# rcsdcard_v1.net
KiCad netlist of a schematic drawn in EAGLE
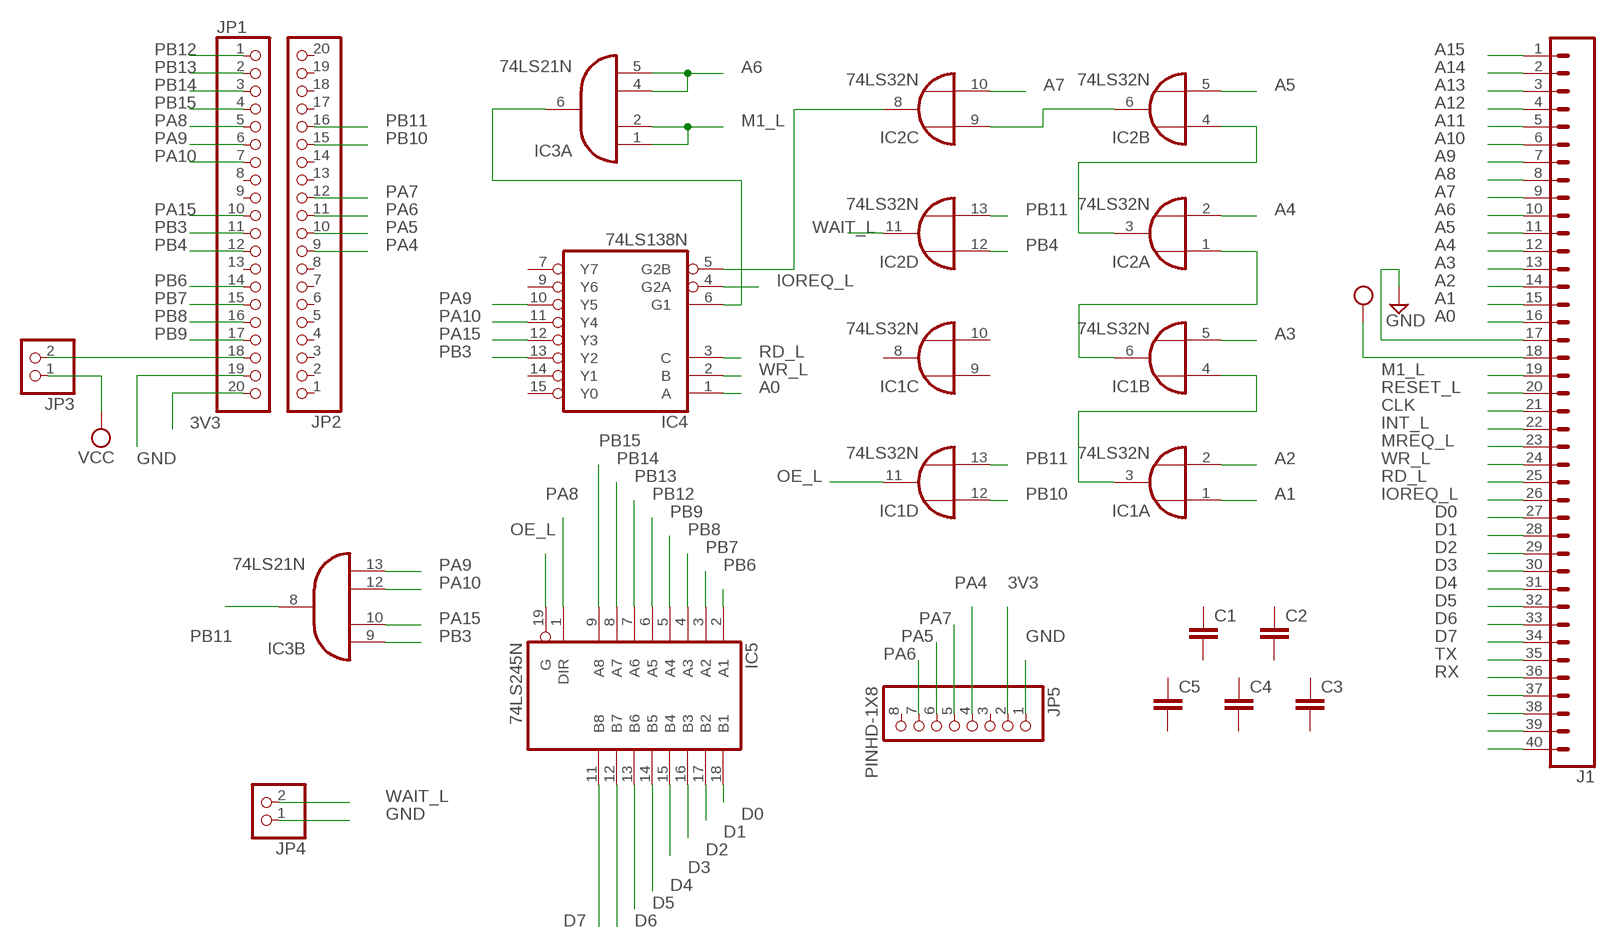
[diagram p0: schematic, sheet 1]

(export (version "E")
  (design (tool "Eeschema 10.0.6"))
  (components
    (comp (ref "C1")
      (value "C-EU050-025X075")
      (footprint "eagle-import:C050-025X075")
      (libsource (lib "eagle-import") (part "C-EU050-025X075"))
    )
    (comp (ref "C2")
      (value "C-EU050-025X075")
      (footprint "eagle-import:C050-025X075")
      (libsource (lib "eagle-import") (part "C-EU050-025X075"))
    )
    (comp (ref "C3")
      (value "C-EU050-025X075")
      (footprint "eagle-import:C050-025X075")
      (libsource (lib "eagle-import") (part "C-EU050-025X075"))
    )
    (comp (ref "C4")
      (value "C-EU050-025X075")
      (footprint "eagle-import:C050-025X075")
      (libsource (lib "eagle-import") (part "C-EU050-025X075"))
    )
    (comp (ref "C5")
      (value "C-EU050-025X075")
      (footprint "eagle-import:C050-025X075")
      (libsource (lib "eagle-import") (part "C-EU050-025X075"))
    )
    (comp (ref "IC1")
      (value "74LS32N")
      (footprint "eagle-import:DIL14")
      (libsource (lib "eagle-import") (part "7432NLS"))
    )
    (comp (ref "IC2")
      (value "74LS32N")
      (footprint "eagle-import:DIL14")
      (libsource (lib "eagle-import") (part "7432NLS"))
    )
    (comp (ref "IC3")
      (value "74LS21N")
      (footprint "eagle-import:DIL14")
      (libsource (lib "eagle-import") (part "7421NLS"))
    )
    (comp (ref "IC4")
      (value "74LS138N")
      (footprint "eagle-import:DIL16")
      (libsource (lib "eagle-import") (part "74138NLS"))
    )
    (comp (ref "IC5")
      (value "74LS245N")
      (footprint "eagle-import:DIL20")
      (libsource (lib "eagle-import") (part "74245NLS"))
    )
    (comp (ref "J1")
      (value "CONN_40OFFSET")
      (footprint "eagle-import:1X40_OFFSET")
      (libsource (lib "eagle-import") (part "CONN_40OFFSET"))
    )
    (comp (ref "JP1")
      (value "PINHD-1X20")
      (footprint "eagle-import:1X20")
      (libsource (lib "eagle-import") (part "PINHD-1X20"))
    )
    (comp (ref "JP2")
      (value "PINHD-1X20")
      (footprint "eagle-import:1X20")
      (libsource (lib "eagle-import") (part "PINHD-1X20"))
    )
    (comp (ref "JP3")
      (value "PINHD-1X2")
      (footprint "eagle-import:1X02")
      (libsource (lib "eagle-import") (part "PINHD-1X2"))
    )
    (comp (ref "JP4")
      (value "PINHD-1X2")
      (footprint "eagle-import:1X02")
      (libsource (lib "eagle-import") (part "PINHD-1X2"))
    )
    (comp (ref "JP5")
      (value "PINHD-1X8")
      (footprint "eagle-import:1X08")
      (libsource (lib "eagle-import") (part "PINHD-1X8"))
    )
  )
  (nets
    (net (code "1") (name "/3V3") (class "Default")
      (node (ref "JP1") (pin "20") (pinfunction "20_20") (pintype "passive"))
      (node (ref "JP5") (pin "2") (pinfunction "2_2") (pintype "passive"))
    )
    (net (code "2") (name "/A0") (class "Default")
      (node (ref "IC4") (pin "1") (pinfunction "A_1") (pintype "input"))
      (node (ref "J1") (pin "16") (pinfunction "16_16") (pintype "passive"))
    )
    (net (code "3") (name "/A1") (class "Default")
      (node (ref "IC1") (pin "1") (pinfunction "I0_1") (pintype "input"))
      (node (ref "J1") (pin "15") (pinfunction "15_15") (pintype "passive"))
    )
    (net (code "4") (name "/A2") (class "Default")
      (node (ref "IC1") (pin "2") (pinfunction "I1_2") (pintype "input"))
      (node (ref "J1") (pin "14") (pinfunction "14_14") (pintype "passive"))
    )
    (net (code "5") (name "/A3") (class "Default")
      (node (ref "IC1") (pin "5") (pinfunction "I1_5") (pintype "input"))
      (node (ref "J1") (pin "13") (pinfunction "13_13") (pintype "passive"))
    )
    (net (code "6") (name "/A4") (class "Default")
      (node (ref "IC2") (pin "2") (pinfunction "I1_2") (pintype "input"))
      (node (ref "J1") (pin "12") (pinfunction "12_12") (pintype "passive"))
    )
    (net (code "7") (name "/A5") (class "Default")
      (node (ref "IC1") (pin "6") (pinfunction "O_6") (pintype "output"))
      (node (ref "IC2") (pin "1") (pinfunction "I0_1") (pintype "input"))
      (node (ref "IC2") (pin "5") (pinfunction "I1_5") (pintype "input"))
      (node (ref "J1") (pin "11") (pinfunction "11_11") (pintype "passive"))
    )
    (net (code "8") (name "/A6") (class "Default")
      (node (ref "IC3") (pin "4") (pinfunction "I2_4") (pintype "input"))
      (node (ref "IC3") (pin "5") (pinfunction "I3_5") (pintype "input"))
      (node (ref "J1") (pin "10") (pinfunction "10_10") (pintype "passive"))
    )
    (net (code "9") (name "/A7") (class "Default")
      (node (ref "IC2") (pin "10") (pinfunction "I1_10") (pintype "input"))
      (node (ref "J1") (pin "9") (pinfunction "9_9") (pintype "passive"))
    )
    (net (code "10") (name "/A8") (class "Default")
      (node (ref "J1") (pin "8") (pinfunction "8_8") (pintype "passive"))
    )
    (net (code "11") (name "/A9") (class "Default")
      (node (ref "J1") (pin "7") (pinfunction "7_7") (pintype "passive"))
    )
    (net (code "12") (name "/A10") (class "Default")
      (node (ref "J1") (pin "6") (pinfunction "6_6") (pintype "passive"))
    )
    (net (code "13") (name "/A11") (class "Default")
      (node (ref "J1") (pin "5") (pinfunction "5_5") (pintype "passive"))
    )
    (net (code "14") (name "/A12") (class "Default")
      (node (ref "J1") (pin "4") (pinfunction "4_4") (pintype "passive"))
    )
    (net (code "15") (name "/A13") (class "Default")
      (node (ref "J1") (pin "3") (pinfunction "3_3") (pintype "passive"))
    )
    (net (code "16") (name "/A14") (class "Default")
      (node (ref "J1") (pin "2") (pinfunction "2_2") (pintype "passive"))
    )
    (net (code "17") (name "/A15") (class "Default")
      (node (ref "J1") (pin "1") (pinfunction "1_1") (pintype "passive"))
    )
    (net (code "18") (name "/CLK") (class "Default")
      (node (ref "J1") (pin "21") (pinfunction "21_21") (pintype "passive"))
    )
    (net (code "19") (name "/D0") (class "Default")
      (node (ref "IC5") (pin "18") (pinfunction "B1_18") (pintype "bidirectional"))
      (node (ref "J1") (pin "27") (pinfunction "27_27") (pintype "passive"))
    )
    (net (code "20") (name "/D1") (class "Default")
      (node (ref "IC5") (pin "17") (pinfunction "B2_17") (pintype "bidirectional"))
      (node (ref "J1") (pin "28") (pinfunction "28_28") (pintype "passive"))
    )
    (net (code "21") (name "/D2") (class "Default")
      (node (ref "IC5") (pin "16") (pinfunction "B3_16") (pintype "bidirectional"))
      (node (ref "J1") (pin "29") (pinfunction "29_29") (pintype "passive"))
    )
    (net (code "22") (name "/D3") (class "Default")
      (node (ref "IC5") (pin "15") (pinfunction "B4_15") (pintype "bidirectional"))
      (node (ref "J1") (pin "30") (pinfunction "30_30") (pintype "passive"))
    )
    (net (code "23") (name "/D4") (class "Default")
      (node (ref "IC5") (pin "14") (pinfunction "B5_14") (pintype "bidirectional"))
      (node (ref "J1") (pin "31") (pinfunction "31_31") (pintype "passive"))
    )
    (net (code "24") (name "/D5") (class "Default")
      (node (ref "IC5") (pin "13") (pinfunction "B6_13") (pintype "bidirectional"))
      (node (ref "J1") (pin "32") (pinfunction "32_32") (pintype "passive"))
    )
    (net (code "25") (name "/D6") (class "Default")
      (node (ref "IC5") (pin "12") (pinfunction "B7_12") (pintype "bidirectional"))
      (node (ref "J1") (pin "33") (pinfunction "33_33") (pintype "passive"))
    )
    (net (code "26") (name "/D7") (class "Default")
      (node (ref "IC5") (pin "11") (pinfunction "B8_11") (pintype "bidirectional"))
      (node (ref "J1") (pin "34") (pinfunction "34_34") (pintype "passive"))
    )
    (net (code "27") (name "/INT_L") (class "Default")
      (node (ref "J1") (pin "22") (pinfunction "22_22") (pintype "passive"))
    )
    (net (code "28") (name "/IOREQ_L") (class "Default")
      (node (ref "IC4") (pin "4") (pinfunction "G2A_4") (pintype "input"))
      (node (ref "J1") (pin "26") (pinfunction "26_26") (pintype "passive"))
    )
    (net (code "29") (name "/M1_L") (class "Default")
      (node (ref "IC3") (pin "1") (pinfunction "I0_1") (pintype "input"))
      (node (ref "IC3") (pin "2") (pinfunction "I1_2") (pintype "input"))
      (node (ref "J1") (pin "19") (pinfunction "19_19") (pintype "passive"))
    )
    (net (code "30") (name "/MREQ_L") (class "Default")
      (node (ref "J1") (pin "23") (pinfunction "23_23") (pintype "passive"))
    )
    (net (code "31") (name "/OE_L") (class "Default")
      (node (ref "IC1") (pin "11") (pinfunction "O_11") (pintype "output"))
      (node (ref "IC5") (pin "19") (pinfunction "G_19") (pintype "input"))
    )
    (net (code "32") (name "/PA4") (class "Default")
      (node (ref "JP2") (pin "9") (pinfunction "9_9") (pintype "passive"))
      (node (ref "JP5") (pin "4") (pinfunction "4_4") (pintype "passive"))
    )
    (net (code "33") (name "/PA5") (class "Default")
      (node (ref "JP2") (pin "10") (pinfunction "10_10") (pintype "passive"))
      (node (ref "JP5") (pin "6") (pinfunction "6_6") (pintype "passive"))
    )
    (net (code "34") (name "/PA6") (class "Default")
      (node (ref "JP2") (pin "11") (pinfunction "11_11") (pintype "passive"))
      (node (ref "JP5") (pin "7") (pinfunction "7_7") (pintype "passive"))
    )
    (net (code "35") (name "/PA7") (class "Default")
      (node (ref "JP2") (pin "12") (pinfunction "12_12") (pintype "passive"))
      (node (ref "JP5") (pin "5") (pinfunction "5_5") (pintype "passive"))
    )
    (net (code "36") (name "/PA8") (class "Default")
      (node (ref "IC5") (pin "1") (pinfunction "DIR_1") (pintype "input"))
      (node (ref "JP1") (pin "5") (pinfunction "5_5") (pintype "passive"))
    )
    (net (code "37") (name "/PA9") (class "Default")
      (node (ref "IC3") (pin "13") (pinfunction "I3_13") (pintype "input"))
      (node (ref "IC4") (pin "10") (pinfunction "Y5_10") (pintype "output"))
      (node (ref "JP1") (pin "6") (pinfunction "6_6") (pintype "passive"))
    )
    (net (code "38") (name "/PA10") (class "Default")
      (node (ref "IC3") (pin "12") (pinfunction "I2_12") (pintype "input"))
      (node (ref "IC4") (pin "11") (pinfunction "Y4_11") (pintype "output"))
      (node (ref "JP1") (pin "7") (pinfunction "7_7") (pintype "passive"))
    )
    (net (code "39") (name "/PA15") (class "Default")
      (node (ref "IC3") (pin "10") (pinfunction "I1_10") (pintype "input"))
      (node (ref "IC4") (pin "12") (pinfunction "Y3_12") (pintype "output"))
      (node (ref "JP1") (pin "10") (pinfunction "10_10") (pintype "passive"))
    )
    (net (code "40") (name "/PB3") (class "Default")
      (node (ref "IC3") (pin "9") (pinfunction "I0_9") (pintype "input"))
      (node (ref "IC4") (pin "13") (pinfunction "Y2_13") (pintype "output"))
      (node (ref "JP1") (pin "11") (pinfunction "11_11") (pintype "passive"))
    )
    (net (code "41") (name "/PB4") (class "Default")
      (node (ref "IC2") (pin "12") (pinfunction "I0_12") (pintype "input"))
      (node (ref "JP1") (pin "12") (pinfunction "12_12") (pintype "passive"))
    )
    (net (code "42") (name "/PB6") (class "Default")
      (node (ref "IC5") (pin "2") (pinfunction "A1_2") (pintype "bidirectional"))
      (node (ref "JP1") (pin "14") (pinfunction "14_14") (pintype "passive"))
    )
    (net (code "43") (name "/PB7") (class "Default")
      (node (ref "IC5") (pin "3") (pinfunction "A2_3") (pintype "bidirectional"))
      (node (ref "JP1") (pin "15") (pinfunction "15_15") (pintype "passive"))
    )
    (net (code "44") (name "/PB8") (class "Default")
      (node (ref "IC5") (pin "4") (pinfunction "A3_4") (pintype "bidirectional"))
      (node (ref "JP1") (pin "16") (pinfunction "16_16") (pintype "passive"))
    )
    (net (code "45") (name "/PB9") (class "Default")
      (node (ref "IC5") (pin "5") (pinfunction "A4_5") (pintype "bidirectional"))
      (node (ref "JP1") (pin "17") (pinfunction "17_17") (pintype "passive"))
    )
    (net (code "46") (name "/PB10") (class "Default")
      (node (ref "IC1") (pin "12") (pinfunction "I0_12") (pintype "input"))
      (node (ref "JP2") (pin "15") (pinfunction "15_15") (pintype "passive"))
    )
    (net (code "47") (name "/PB11") (class "Default")
      (node (ref "IC1") (pin "13") (pinfunction "I1_13") (pintype "input"))
      (node (ref "IC2") (pin "13") (pinfunction "I1_13") (pintype "input"))
      (node (ref "IC3") (pin "8") (pinfunction "O_8") (pintype "output"))
      (node (ref "JP2") (pin "16") (pinfunction "16_16") (pintype "passive"))
    )
    (net (code "48") (name "/PB12") (class "Default")
      (node (ref "IC5") (pin "6") (pinfunction "A5_6") (pintype "bidirectional"))
      (node (ref "JP1") (pin "1") (pinfunction "1_1") (pintype "passive"))
    )
    (net (code "49") (name "/PB13") (class "Default")
      (node (ref "IC5") (pin "7") (pinfunction "A6_7") (pintype "bidirectional"))
      (node (ref "JP1") (pin "2") (pinfunction "2_2") (pintype "passive"))
    )
    (net (code "50") (name "/PB14") (class "Default")
      (node (ref "IC5") (pin "8") (pinfunction "A7_8") (pintype "bidirectional"))
      (node (ref "JP1") (pin "3") (pinfunction "3_3") (pintype "passive"))
    )
    (net (code "51") (name "/PB15") (class "Default")
      (node (ref "IC5") (pin "9") (pinfunction "A8_9") (pintype "bidirectional"))
      (node (ref "JP1") (pin "4") (pinfunction "4_4") (pintype "passive"))
    )
    (net (code "52") (name "/RD_L") (class "Default")
      (node (ref "IC4") (pin "3") (pinfunction "C_3") (pintype "input"))
      (node (ref "J1") (pin "25") (pinfunction "25_25") (pintype "passive"))
    )
    (net (code "53") (name "/RESET_L") (class "Default")
      (node (ref "J1") (pin "20") (pinfunction "20_20") (pintype "passive"))
    )
    (net (code "54") (name "/RX") (class "Default")
      (node (ref "J1") (pin "36") (pinfunction "36_36") (pintype "passive"))
    )
    (net (code "55") (name "/TX") (class "Default")
      (node (ref "J1") (pin "35") (pinfunction "35_35") (pintype "passive"))
    )
    (net (code "56") (name "/WAIT_L") (class "Default")
      (node (ref "IC2") (pin "11") (pinfunction "O_11") (pintype "output"))
      (node (ref "JP4") (pin "2") (pinfunction "2_2") (pintype "passive"))
    )
    (net (code "57") (name "/WR_L") (class "Default")
      (node (ref "IC4") (pin "2") (pinfunction "B_2") (pintype "input"))
      (node (ref "J1") (pin "24") (pinfunction "24_24") (pintype "passive"))
    )
    (net (code "58") (name "GND") (class "Default")
      (node (ref "J1") (pin "17") (pinfunction "17_17") (pintype "passive"))
      (node (ref "JP1") (pin "19") (pinfunction "19_19") (pintype "passive"))
      (node (ref "JP4") (pin "1") (pinfunction "1_1") (pintype "passive"))
      (node (ref "JP5") (pin "1") (pinfunction "1_1") (pintype "passive"))
    )
    (net (code "59") (name "Net-(IC1A-O)") (class "Default")
      (node (ref "IC1") (pin "3") (pinfunction "O_3") (pintype "output"))
      (node (ref "IC1") (pin "4") (pinfunction "I0_4") (pintype "input"))
    )
    (net (code "60") (name "Net-(IC2A-O)") (class "Default")
      (node (ref "IC2") (pin "3") (pinfunction "O_3") (pintype "output"))
      (node (ref "IC2") (pin "4") (pinfunction "I0_4") (pintype "input"))
    )
    (net (code "61") (name "Net-(IC2B-O)") (class "Default")
      (node (ref "IC2") (pin "6") (pinfunction "O_6") (pintype "output"))
      (node (ref "IC2") (pin "9") (pinfunction "I0_9") (pintype "input"))
    )
    (net (code "62") (name "Net-(IC2C-O)") (class "Default")
      (node (ref "IC2") (pin "8") (pinfunction "O_8") (pintype "output"))
      (node (ref "IC4") (pin "5") (pinfunction "G2B_5") (pintype "input"))
    )
    (net (code "63") (name "Net-(IC3A-O)") (class "Default")
      (node (ref "IC3") (pin "6") (pinfunction "O_6") (pintype "output"))
      (node (ref "IC4") (pin "6") (pinfunction "G1_6") (pintype "input"))
    )
    (net (code "64") (name "Net-(JP1-Pad18)") (class "Default")
      (node (ref "JP1") (pin "18") (pinfunction "18_18") (pintype "passive"))
      (node (ref "JP3") (pin "2") (pinfunction "2_2") (pintype "passive"))
    )
    (net (code "65") (name "VCC") (class "Default")
      (node (ref "J1") (pin "18") (pinfunction "18_18") (pintype "passive"))
      (node (ref "JP3") (pin "1") (pinfunction "1_1") (pintype "passive"))
    )
    (net (code "66") (name "unconnected-(C1-Pad1)") (class "Default")
      (node (ref "C1") (pin "1") (pinfunction "1_1") (pintype "passive"))
    )
    (net (code "67") (name "unconnected-(C1-Pad2)") (class "Default")
      (node (ref "C1") (pin "2") (pinfunction "2_2") (pintype "passive"))
    )
    (net (code "68") (name "unconnected-(C2-Pad1)") (class "Default")
      (node (ref "C2") (pin "1") (pinfunction "1_1") (pintype "passive"))
    )
    (net (code "69") (name "unconnected-(C2-Pad2)") (class "Default")
      (node (ref "C2") (pin "2") (pinfunction "2_2") (pintype "passive"))
    )
    (net (code "70") (name "unconnected-(C3-Pad1)") (class "Default")
      (node (ref "C3") (pin "1") (pinfunction "1_1") (pintype "passive"))
    )
    (net (code "71") (name "unconnected-(C3-Pad2)") (class "Default")
      (node (ref "C3") (pin "2") (pinfunction "2_2") (pintype "passive"))
    )
    (net (code "72") (name "unconnected-(C4-Pad1)") (class "Default")
      (node (ref "C4") (pin "1") (pinfunction "1_1") (pintype "passive"))
    )
    (net (code "73") (name "unconnected-(C4-Pad2)") (class "Default")
      (node (ref "C4") (pin "2") (pinfunction "2_2") (pintype "passive"))
    )
    (net (code "74") (name "unconnected-(C5-Pad1)") (class "Default")
      (node (ref "C5") (pin "1") (pinfunction "1_1") (pintype "passive"))
    )
    (net (code "75") (name "unconnected-(C5-Pad2)") (class "Default")
      (node (ref "C5") (pin "2") (pinfunction "2_2") (pintype "passive"))
    )
    (net (code "76") (name "unconnected-(IC1C-I0-Pad9)") (class "Default")
      (node (ref "IC1") (pin "9") (pinfunction "I0_9") (pintype "input"))
    )
    (net (code "77") (name "unconnected-(IC1C-I1-Pad10)") (class "Default")
      (node (ref "IC1") (pin "10") (pinfunction "I1_10") (pintype "input"))
    )
    (net (code "78") (name "unconnected-(IC1C-O-Pad8)") (class "Default")
      (node (ref "IC1") (pin "8") (pinfunction "O_8") (pintype "output"))
    )
    (net (code "79") (name "unconnected-(IC4A-Y0-Pad15)") (class "Default")
      (node (ref "IC4") (pin "15") (pinfunction "Y0_15") (pintype "output"))
    )
    (net (code "80") (name "unconnected-(IC4A-Y1-Pad14)") (class "Default")
      (node (ref "IC4") (pin "14") (pinfunction "Y1_14") (pintype "output"))
    )
    (net (code "81") (name "unconnected-(IC4A-Y6-Pad9)") (class "Default")
      (node (ref "IC4") (pin "9") (pinfunction "Y6_9") (pintype "output"))
    )
    (net (code "82") (name "unconnected-(IC4A-Y7-Pad7)") (class "Default")
      (node (ref "IC4") (pin "7") (pinfunction "Y7_7") (pintype "output"))
    )
    (net (code "83") (name "unconnected-(J1-Pad37)") (class "Default")
      (node (ref "J1") (pin "37") (pinfunction "37_37") (pintype "passive"))
    )
    (net (code "84") (name "unconnected-(J1-Pad38)") (class "Default")
      (node (ref "J1") (pin "38") (pinfunction "38_38") (pintype "passive"))
    )
    (net (code "85") (name "unconnected-(J1-Pad39)") (class "Default")
      (node (ref "J1") (pin "39") (pinfunction "39_39") (pintype "passive"))
    )
    (net (code "86") (name "unconnected-(J1-Pad40)") (class "Default")
      (node (ref "J1") (pin "40") (pinfunction "40_40") (pintype "passive"))
    )
    (net (code "87") (name "unconnected-(JP1-Pad8)") (class "Default")
      (node (ref "JP1") (pin "8") (pinfunction "8_8") (pintype "passive"))
    )
    (net (code "88") (name "unconnected-(JP1-Pad9)") (class "Default")
      (node (ref "JP1") (pin "9") (pinfunction "9_9") (pintype "passive"))
    )
    (net (code "89") (name "unconnected-(JP1-Pad13)") (class "Default")
      (node (ref "JP1") (pin "13") (pinfunction "13_13") (pintype "passive"))
    )
    (net (code "90") (name "unconnected-(JP2-Pad1)") (class "Default")
      (node (ref "JP2") (pin "1") (pinfunction "1_1") (pintype "passive"))
    )
    (net (code "91") (name "unconnected-(JP2-Pad2)") (class "Default")
      (node (ref "JP2") (pin "2") (pinfunction "2_2") (pintype "passive"))
    )
    (net (code "92") (name "unconnected-(JP2-Pad3)") (class "Default")
      (node (ref "JP2") (pin "3") (pinfunction "3_3") (pintype "passive"))
    )
    (net (code "93") (name "unconnected-(JP2-Pad4)") (class "Default")
      (node (ref "JP2") (pin "4") (pinfunction "4_4") (pintype "passive"))
    )
    (net (code "94") (name "unconnected-(JP2-Pad5)") (class "Default")
      (node (ref "JP2") (pin "5") (pinfunction "5_5") (pintype "passive"))
    )
    (net (code "95") (name "unconnected-(JP2-Pad6)") (class "Default")
      (node (ref "JP2") (pin "6") (pinfunction "6_6") (pintype "passive"))
    )
    (net (code "96") (name "unconnected-(JP2-Pad7)") (class "Default")
      (node (ref "JP2") (pin "7") (pinfunction "7_7") (pintype "passive"))
    )
    (net (code "97") (name "unconnected-(JP2-Pad8)") (class "Default")
      (node (ref "JP2") (pin "8") (pinfunction "8_8") (pintype "passive"))
    )
    (net (code "98") (name "unconnected-(JP2-Pad13)") (class "Default")
      (node (ref "JP2") (pin "13") (pinfunction "13_13") (pintype "passive"))
    )
    (net (code "99") (name "unconnected-(JP2-Pad14)") (class "Default")
      (node (ref "JP2") (pin "14") (pinfunction "14_14") (pintype "passive"))
    )
    (net (code "100") (name "unconnected-(JP2-Pad17)") (class "Default")
      (node (ref "JP2") (pin "17") (pinfunction "17_17") (pintype "passive"))
    )
    (net (code "101") (name "unconnected-(JP2-Pad18)") (class "Default")
      (node (ref "JP2") (pin "18") (pinfunction "18_18") (pintype "passive"))
    )
    (net (code "102") (name "unconnected-(JP2-Pad19)") (class "Default")
      (node (ref "JP2") (pin "19") (pinfunction "19_19") (pintype "passive"))
    )
    (net (code "103") (name "unconnected-(JP2-Pad20)") (class "Default")
      (node (ref "JP2") (pin "20") (pinfunction "20_20") (pintype "passive"))
    )
    (net (code "104") (name "unconnected-(JP5-Pad3)") (class "Default")
      (node (ref "JP5") (pin "3") (pinfunction "3_3") (pintype "passive"))
    )
    (net (code "105") (name "unconnected-(JP5-Pad8)") (class "Default")
      (node (ref "JP5") (pin "8") (pinfunction "8_8") (pintype "passive"))
    )
  )
)
